# SCH_ZX_WiFi_2023-12-15.net
KiCad netlist of a schematic drawn in EasyEDA
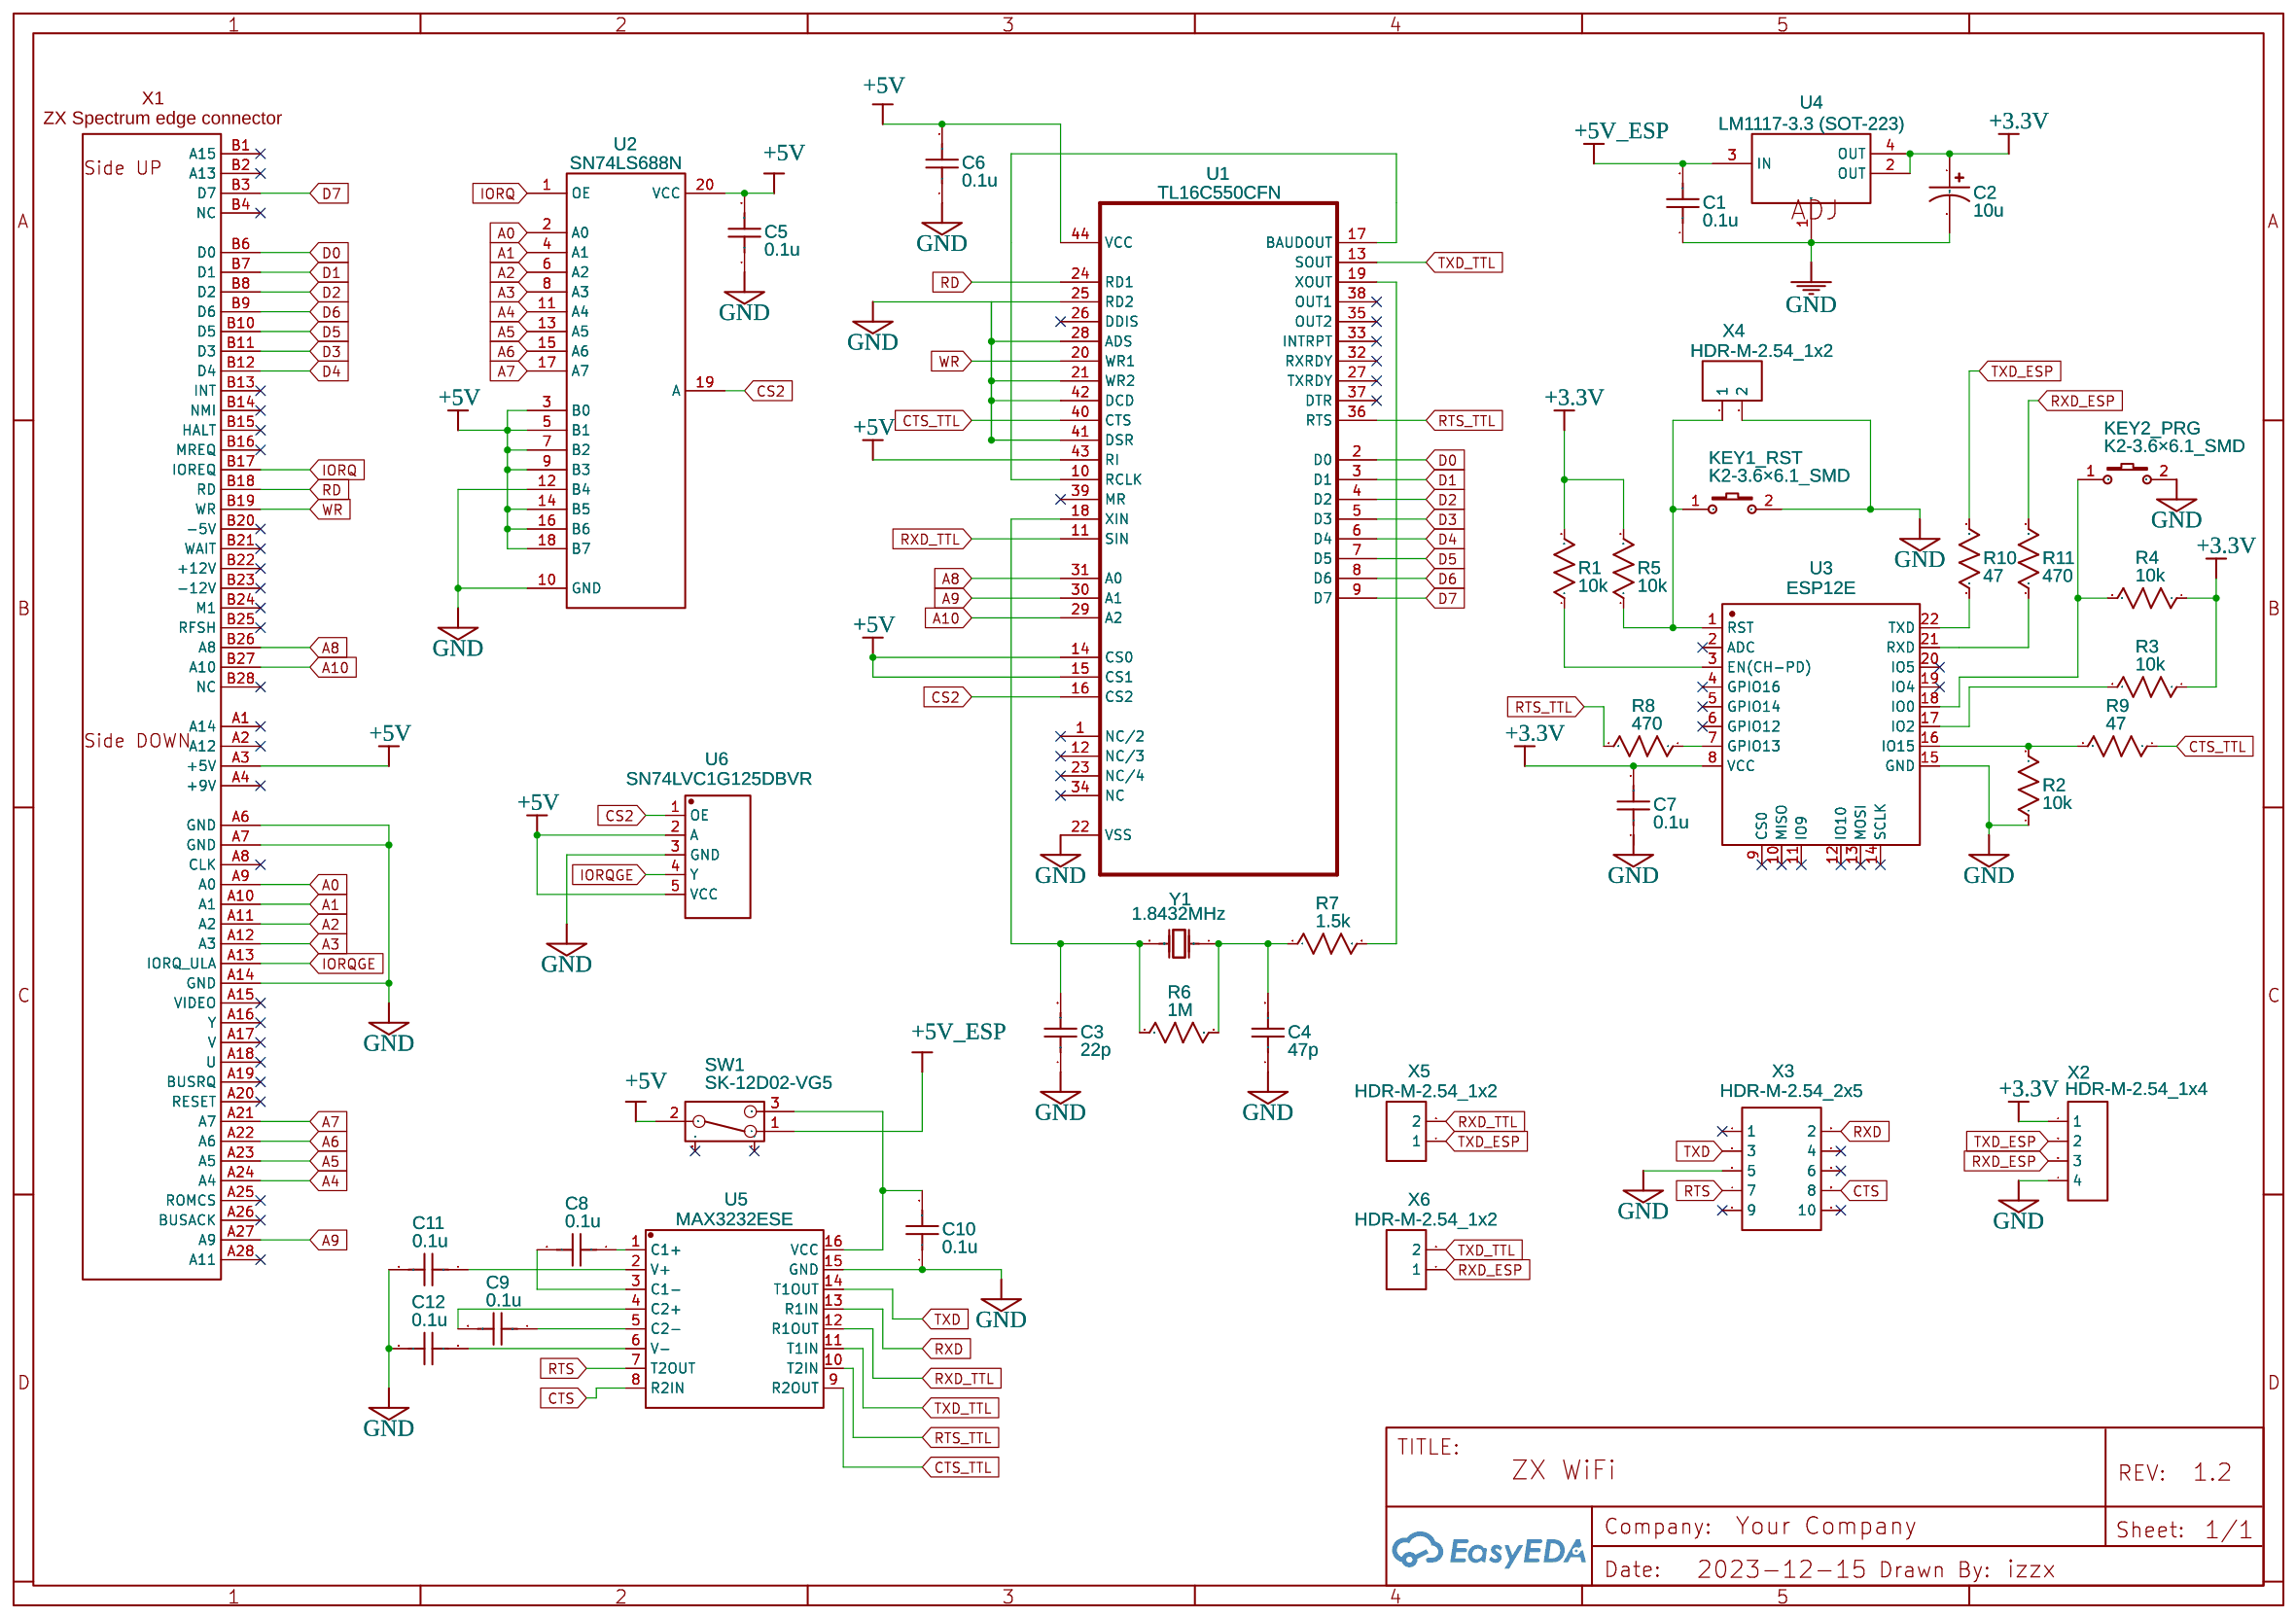
[diagram p0: schematic sheet]

(export (version "E")
  (design (tool "Eeschema 10.0.6"))
  (components
    (comp (ref "C1") (value "0.1u") (libsource (lib "") (part "C_0805_US_1")))
    (comp (ref "C2") (value "10u") (libsource (lib "") (part "C_Tan_SMD_A_US")))
    (comp (ref "C3") (value "22p") (libsource (lib "") (part "C_0805_US_1")))
    (comp (ref "C4") (value "47p") (libsource (lib "") (part "C_0805_US_1")))
    (comp (ref "C5") (value "0.1u") (libsource (lib "") (part "C_0805_US_1")))
    (comp (ref "C6") (value "0.1u") (libsource (lib "") (part "C_0805_US_1")))
    (comp (ref "C7") (value "0.1u") (libsource (lib "") (part "C_0805_US_1")))
    (comp (ref "C8") (value "0.1u") (libsource (lib "") (part "C_0805_US")))
    (comp (ref "C9") (value "0.1u") (libsource (lib "") (part "C_0805_US")))
    (comp (ref "C10") (value "0.1u") (libsource (lib "") (part "C_0805_US_1")))
    (comp (ref "C11") (value "0.1u") (libsource (lib "") (part "C_0805_US")))
    (comp (ref "C12") (value "0.1u") (libsource (lib "") (part "C_0805_US")))
    (comp (ref "KEY1_RST")
      (value "K2-3.6×6.1_SMD")
      (fields (field (name "Manufacturer Part") "K2-1107ST-A4SW-06"))
      (libsource (lib "") (part "K2-3.6×6.1_SMD"))
    )
    (comp (ref "KEY2_PRG")
      (value "K2-3.6×6.1_SMD")
      (fields (field (name "Manufacturer Part") "K2-1107ST-A4SW-06"))
      (libsource (lib "") (part "K2-3.6×6.1_SMD_1"))
    )
    (comp (ref "R1") (value "10k") (libsource (lib "") (part "R_0805_US_1")))
    (comp (ref "R2") (value "10k") (libsource (lib "") (part "R_0805_US_1")))
    (comp (ref "R3") (value "10k") (libsource (lib "") (part "R_0805_US_2")))
    (comp (ref "R4") (value "10k") (libsource (lib "") (part "R_0805_US_2")))
    (comp (ref "R5") (value "10k") (libsource (lib "") (part "R_0805_US_1")))
    (comp (ref "R6") (value "1M") (libsource (lib "") (part "R_0805_US")))
    (comp (ref "R7") (value "1.5k") (libsource (lib "") (part "R_0805_US")))
    (comp (ref "R8") (value "470") (libsource (lib "") (part "R_0805_US_2")))
    (comp (ref "R9") (value "47") (libsource (lib "") (part "R_0805_US_2")))
    (comp (ref "R10") (value "47") (libsource (lib "") (part "R_0805_US_1")))
    (comp (ref "R11") (value "470") (libsource (lib "") (part "R_0805_US_1")))
    (comp (ref "SW1")
      (value "SK-12D02-VG5")
      (fields (field (name "Manufacturer") "Rectangular Connectors - Contacts"))
      (libsource (lib "") (part "SK-12D02-VG5"))
    )
    (comp (ref "U1") (value "TL16C550CFN") (libsource (lib "") (part "TL16C550CFN")))
    (comp (ref "U2") (value "SN74LS688N") (libsource (lib "") (part "SN74LS688N")))
    (comp (ref "U3") (value "ESP12E") (libsource (lib "") (part "ESP12E/F")))
    (comp (ref "U4")
      (value "LM1117-3.3 (SOT-223)")
      (fields (field (name "Manufacturer Part") "LM317G-AA3-R") (field (name "Manufacturer") "UTC"))
      (libsource (lib "") (part "LM317(SOT-223)"))
    )
    (comp (ref "U5")
      (value "MAX3232ESE")
      (fields (field (name "Manufacturer") "UMW(友台半导体)"))
      (libsource (lib "") (part "MAX3232ESE"))
    )
    (comp (ref "U6")
      (value "SN74LVC1G125DBVR")
      (fields (field (name "Manufacturer") "TI(德州仪器)"))
      (libsource (lib "") (part "SN74LVC1G125DBVR"))
    )
    (comp (ref "X1") (value "ZX SPECTRUM CONNECTOR") (libsource (lib "") (part "ZX SPECTRUM CONNECTOR")))
    (comp (ref "X2") (value "HDR-M-2.54_1x4") (libsource (lib "") (part "HDR-M-2.54_1x4")))
    (comp (ref "X3") (value "HDR-M-2.54_2x5") (libsource (lib "") (part "HDR-M-2.54_2x5")))
    (comp (ref "X4") (value "HDR-M-2.54_1x2") (libsource (lib "") (part "HDR-M-2.54_1x2")))
    (comp (ref "X5") (value "HDR-M-2.54_1x2") (libsource (lib "") (part "HDR-M-2.54_1x2_1")))
    (comp (ref "X6") (value "HDR-M-2.54_1x2") (libsource (lib "") (part "HDR-M-2.54_1x2_1")))
    (comp (ref "Y1")
      (value "1.8432MHz")
      (fields (field (name "Manufacturer Part") "X49UD3579MSD2SC") (field (name "Manufacturer") "ValuePro"))
      (libsource (lib "") (part "X49UD3579MSD2SC"))
    )
  )
  (nets
    (net (code "1") (name "+3.3V") (class "Default")
      (node (ref "C2") (pin "1") (pinfunction "1_1") (pintype "unspecified"))
      (node (ref "C7") (pin "2") (pinfunction "2_2") (pintype "unspecified"))
      (node (ref "R1") (pin "2") (pinfunction "2_2") (pintype "unspecified"))
      (node (ref "R3") (pin "1") (pinfunction "1_1") (pintype "unspecified"))
      (node (ref "R4") (pin "1") (pinfunction "1_1") (pintype "unspecified"))
      (node (ref "R5") (pin "2") (pinfunction "2_2") (pintype "unspecified"))
      (node (ref "U3") (pin "8") (pinfunction "VCC_8") (pintype "unspecified"))
      (node (ref "U4") (pin "2") (pinfunction "OUT_2") (pintype "passive"))
      (node (ref "U4") (pin "4") (pinfunction "OUT_4") (pintype "passive"))
      (node (ref "X2") (pin "1") (pinfunction "1_1") (pintype "unspecified"))
    )
    (net (code "2") (name "+5V") (class "Default")
      (node (ref "C5") (pin "2") (pinfunction "2_2") (pintype "unspecified"))
      (node (ref "C6") (pin "2") (pinfunction "2_2") (pintype "unspecified"))
      (node (ref "SW1") (pin "2") (pinfunction "2_2") (pintype "unspecified"))
      (node (ref "U1") (pin "14") (pinfunction "CS0_14") (pintype "input"))
      (node (ref "U1") (pin "15") (pinfunction "CS1_15") (pintype "input"))
      (node (ref "U1") (pin "43") (pinfunction "RI_43") (pintype "input"))
      (node (ref "U1") (pin "44") (pinfunction "VCC_44") (pintype "passive"))
      (node (ref "U2") (pin "14") (pinfunction "B5_14") (pintype "unspecified"))
      (node (ref "U2") (pin "16") (pinfunction "B6_16") (pintype "unspecified"))
      (node (ref "U2") (pin "18") (pinfunction "B7_18") (pintype "unspecified"))
      (node (ref "U2") (pin "20") (pinfunction "VCC_20") (pintype "passive"))
      (node (ref "U2") (pin "3") (pinfunction "B0_3") (pintype "unspecified"))
      (node (ref "U2") (pin "5") (pinfunction "B1_5") (pintype "unspecified"))
      (node (ref "U2") (pin "7") (pinfunction "B2_7") (pintype "unspecified"))
      (node (ref "U2") (pin "9") (pinfunction "B3_9") (pintype "unspecified"))
      (node (ref "U6") (pin "2") (pinfunction "A_2") (pintype "unspecified"))
      (node (ref "U6") (pin "5") (pinfunction "VCC_5") (pintype "unspecified"))
      (node (ref "X1") (pin "A3") (pinfunction "+5V_A3") (pintype "unspecified"))
    )
    (net (code "3") (name "+5V_ESP") (class "Default")
      (node (ref "C1") (pin "2") (pinfunction "2_2") (pintype "unspecified"))
      (node (ref "SW1") (pin "1") (pinfunction "1_1") (pintype "unspecified"))
      (node (ref "U4") (pin "3") (pinfunction "IN_3") (pintype "passive"))
    )
    (net (code "4") (name "A0") (class "Default")
      (node (ref "U2") (pin "2") (pinfunction "A0_2") (pintype "unspecified"))
      (node (ref "X1") (pin "A9") (pinfunction "A0_A9") (pintype "unspecified"))
    )
    (net (code "5") (name "A1") (class "Default")
      (node (ref "U2") (pin "4") (pinfunction "A1_4") (pintype "unspecified"))
      (node (ref "X1") (pin "A10") (pinfunction "A1_A10") (pintype "unspecified"))
    )
    (net (code "6") (name "A2") (class "Default")
      (node (ref "U2") (pin "6") (pinfunction "A2_6") (pintype "unspecified"))
      (node (ref "X1") (pin "A11") (pinfunction "A2_A11") (pintype "unspecified"))
    )
    (net (code "7") (name "A3") (class "Default")
      (node (ref "U2") (pin "8") (pinfunction "A3_8") (pintype "unspecified"))
      (node (ref "X1") (pin "A12") (pinfunction "A3_A12") (pintype "unspecified"))
    )
    (net (code "8") (name "A4") (class "Default")
      (node (ref "U2") (pin "11") (pinfunction "A4_11") (pintype "unspecified"))
      (node (ref "X1") (pin "A24") (pinfunction "A4_A24") (pintype "unspecified"))
    )
    (net (code "9") (name "A5") (class "Default")
      (node (ref "U2") (pin "13") (pinfunction "A5_13") (pintype "unspecified"))
      (node (ref "X1") (pin "A23") (pinfunction "A5_A23") (pintype "unspecified"))
    )
    (net (code "10") (name "A6") (class "Default")
      (node (ref "U2") (pin "15") (pinfunction "A6_15") (pintype "unspecified"))
      (node (ref "X1") (pin "A22") (pinfunction "A6_A22") (pintype "unspecified"))
    )
    (net (code "11") (name "A7") (class "Default")
      (node (ref "U2") (pin "17") (pinfunction "A7_17") (pintype "unspecified"))
      (node (ref "X1") (pin "A21") (pinfunction "A7_A21") (pintype "unspecified"))
    )
    (net (code "12") (name "A8") (class "Default")
      (node (ref "U1") (pin "31") (pinfunction "A0_31") (pintype "input"))
      (node (ref "X1") (pin "B26") (pinfunction "A8_B26") (pintype "unspecified"))
    )
    (net (code "13") (name "A9") (class "Default")
      (node (ref "U1") (pin "30") (pinfunction "A1_30") (pintype "input"))
      (node (ref "X1") (pin "A27") (pinfunction "A9_A27") (pintype "unspecified"))
    )
    (net (code "14") (name "A10") (class "Default")
      (node (ref "U1") (pin "29") (pinfunction "A2_29") (pintype "input"))
      (node (ref "X1") (pin "B27") (pinfunction "A10_B27") (pintype "unspecified"))
    )
    (net (code "15") (name "CS2") (class "Default")
      (node (ref "U1") (pin "16") (pinfunction "CS2_16") (pintype "input"))
      (node (ref "U2") (pin "19") (pinfunction "A_19") (pintype "output"))
      (node (ref "U6") (pin "1") (pinfunction "OE_1") (pintype "unspecified"))
    )
    (net (code "16") (name "CTS") (class "Default")
      (node (ref "U5") (pin "8") (pinfunction "R2IN_8") (pintype "unspecified"))
      (node (ref "X3") (pin "8") (pinfunction "8_8") (pintype "unspecified"))
    )
    (net (code "17") (name "CTS_TTL") (class "Default")
      (node (ref "R9") (pin "1") (pinfunction "1_1") (pintype "unspecified"))
      (node (ref "U1") (pin "40") (pinfunction "CTS_40") (pintype "input"))
      (node (ref "U5") (pin "9") (pinfunction "R2OUT_9") (pintype "unspecified"))
    )
    (net (code "18") (name "D0") (class "Default")
      (node (ref "U1") (pin "2") (pinfunction "D0_2") (pintype "unspecified"))
      (node (ref "X1") (pin "B6") (pinfunction "D0_B6") (pintype "bidirectional"))
    )
    (net (code "19") (name "D1") (class "Default")
      (node (ref "U1") (pin "3") (pinfunction "D1_3") (pintype "unspecified"))
      (node (ref "X1") (pin "B7") (pinfunction "D1_B7") (pintype "bidirectional"))
    )
    (net (code "20") (name "D2") (class "Default")
      (node (ref "U1") (pin "4") (pinfunction "D2_4") (pintype "unspecified"))
      (node (ref "X1") (pin "B8") (pinfunction "D2_B8") (pintype "bidirectional"))
    )
    (net (code "21") (name "D3") (class "Default")
      (node (ref "U1") (pin "5") (pinfunction "D3_5") (pintype "unspecified"))
      (node (ref "X1") (pin "B11") (pinfunction "D3_B11") (pintype "unspecified"))
    )
    (net (code "22") (name "D4") (class "Default")
      (node (ref "U1") (pin "6") (pinfunction "D4_6") (pintype "unspecified"))
      (node (ref "X1") (pin "B12") (pinfunction "D4_B12") (pintype "unspecified"))
    )
    (net (code "23") (name "D5") (class "Default")
      (node (ref "U1") (pin "7") (pinfunction "D5_7") (pintype "unspecified"))
      (node (ref "X1") (pin "B10") (pinfunction "D5_B10") (pintype "bidirectional"))
    )
    (net (code "24") (name "D6") (class "Default")
      (node (ref "U1") (pin "8") (pinfunction "D6_8") (pintype "unspecified"))
      (node (ref "X1") (pin "B9") (pinfunction "D6_B9") (pintype "unspecified"))
    )
    (net (code "25") (name "D7") (class "Default")
      (node (ref "U1") (pin "9") (pinfunction "D7_9") (pintype "unspecified"))
      (node (ref "X1") (pin "B3") (pinfunction "D7_B3") (pintype "bidirectional"))
    )
    (net (code "26") (name "GND") (class "Default")
      (node (ref "C1") (pin "1") (pinfunction "1_1") (pintype "unspecified"))
      (node (ref "C10") (pin "1") (pinfunction "1_1") (pintype "unspecified"))
      (node (ref "C11") (pin "2") (pinfunction "2_2") (pintype "unspecified"))
      (node (ref "C12") (pin "2") (pinfunction "2_2") (pintype "unspecified"))
      (node (ref "C2") (pin "2") (pinfunction "2_2") (pintype "unspecified"))
      (node (ref "C3") (pin "1") (pinfunction "1_1") (pintype "unspecified"))
      (node (ref "C4") (pin "1") (pinfunction "1_1") (pintype "unspecified"))
      (node (ref "C5") (pin "1") (pinfunction "1_1") (pintype "unspecified"))
      (node (ref "C6") (pin "1") (pinfunction "1_1") (pintype "unspecified"))
      (node (ref "C7") (pin "1") (pinfunction "1_1") (pintype "unspecified"))
      (node (ref "KEY1_RST") (pin "2") (pinfunction "2_2") (pintype "unspecified"))
      (node (ref "KEY2_PRG") (pin "2") (pinfunction "2_2") (pintype "unspecified"))
      (node (ref "R2") (pin "1") (pinfunction "1_1") (pintype "unspecified"))
      (node (ref "U1") (pin "21") (pinfunction "WR2_21") (pintype "input"))
      (node (ref "U1") (pin "22") (pinfunction "VSS_22") (pintype "passive"))
      (node (ref "U1") (pin "25") (pinfunction "RD2_25") (pintype "input"))
      (node (ref "U1") (pin "28") (pinfunction "ADS_28") (pintype "input"))
      (node (ref "U1") (pin "41") (pinfunction "DSR_41") (pintype "input"))
      (node (ref "U1") (pin "42") (pinfunction "DCD_42") (pintype "input"))
      (node (ref "U2") (pin "10") (pinfunction "GND_10") (pintype "passive"))
      (node (ref "U2") (pin "12") (pinfunction "B4_12") (pintype "unspecified"))
      (node (ref "U3") (pin "15") (pinfunction "GND_15") (pintype "unspecified"))
      (node (ref "U4") (pin "1") (pinfunction "ADJ_1") (pintype "passive"))
      (node (ref "U5") (pin "15") (pinfunction "GND_15") (pintype "unspecified"))
      (node (ref "U6") (pin "3") (pinfunction "GND_3") (pintype "unspecified"))
      (node (ref "X1") (pin "A14") (pinfunction "GND_A14") (pintype "unspecified"))
      (node (ref "X1") (pin "A6") (pinfunction "GND_A6") (pintype "unspecified"))
      (node (ref "X1") (pin "A7") (pinfunction "GND_A7") (pintype "unspecified"))
      (node (ref "X2") (pin "4") (pinfunction "4_4") (pintype "unspecified"))
      (node (ref "X3") (pin "5") (pinfunction "5_5") (pintype "unspecified"))
      (node (ref "X4") (pin "2") (pinfunction "2_2") (pintype "unspecified"))
    )
    (net (code "27") (name "IORQ") (class "Default")
      (node (ref "U2") (pin "1") (pinfunction "OE_1") (pintype "unspecified"))
      (node (ref "X1") (pin "B17") (pinfunction "IOREQ_B17") (pintype "unspecified"))
    )
    (net (code "28") (name "IORQGE") (class "Default")
      (node (ref "U6") (pin "4") (pinfunction "Y_4") (pintype "unspecified"))
      (node (ref "X1") (pin "A13") (pinfunction "IORQ_ULA_A13") (pintype "unspecified"))
    )
    (net (code "29") (name "Net-(U1-BAUDOUT)") (class "Default")
      (node (ref "U1") (pin "10") (pinfunction "RCLK_10") (pintype "input"))
      (node (ref "U1") (pin "17") (pinfunction "BAUDOUT_17") (pintype "output"))
    )
    (net (code "30") (name "Net-(U1-XIN)") (class "Default")
      (node (ref "C3") (pin "2") (pinfunction "2_2") (pintype "unspecified"))
      (node (ref "R6") (pin "1") (pinfunction "1_1") (pintype "unspecified"))
      (node (ref "U1") (pin "18") (pinfunction "XIN_18") (pintype "input"))
      (node (ref "Y1") (pin "2") (pinfunction "OSC2_2") (pintype "input"))
    )
    (net (code "31") (name "Net-(U1-XOUT)") (class "Default")
      (node (ref "R7") (pin "2") (pinfunction "2_2") (pintype "unspecified"))
      (node (ref "U1") (pin "19") (pinfunction "XOUT_19") (pintype "output"))
    )
    (net (code "32") (name "Net-(U3-EN(CH-PD))") (class "Default")
      (node (ref "R1") (pin "1") (pinfunction "1_1") (pintype "unspecified"))
      (node (ref "U3") (pin "3") (pinfunction "EN(CH-PD)_3") (pintype "unspecified"))
    )
    (net (code "33") (name "Net-(U3-GPIO13)") (class "Default")
      (node (ref "R8") (pin "1") (pinfunction "1_1") (pintype "unspecified"))
      (node (ref "U3") (pin "7") (pinfunction "GPIO13_7") (pintype "unspecified"))
    )
    (net (code "34") (name "Net-(U3-IO0)") (class "Default")
      (node (ref "KEY2_PRG") (pin "1") (pinfunction "1_1") (pintype "unspecified"))
      (node (ref "R4") (pin "2") (pinfunction "2_2") (pintype "unspecified"))
      (node (ref "U3") (pin "18") (pinfunction "IO0_18") (pintype "unspecified"))
    )
    (net (code "35") (name "Net-(U3-IO2)") (class "Default")
      (node (ref "R3") (pin "2") (pinfunction "2_2") (pintype "unspecified"))
      (node (ref "U3") (pin "17") (pinfunction "IO2_17") (pintype "unspecified"))
    )
    (net (code "36") (name "Net-(U3-IO15)") (class "Default")
      (node (ref "R2") (pin "2") (pinfunction "2_2") (pintype "unspecified"))
      (node (ref "R9") (pin "2") (pinfunction "2_2") (pintype "unspecified"))
      (node (ref "U3") (pin "16") (pinfunction "IO15_16") (pintype "unspecified"))
    )
    (net (code "37") (name "Net-(U3-RST)") (class "Default")
      (node (ref "KEY1_RST") (pin "1") (pinfunction "1_1") (pintype "unspecified"))
      (node (ref "R5") (pin "1") (pinfunction "1_1") (pintype "unspecified"))
      (node (ref "U3") (pin "1") (pinfunction "RST_1") (pintype "unspecified"))
      (node (ref "X4") (pin "1") (pinfunction "1_1") (pintype "unspecified"))
    )
    (net (code "38") (name "Net-(U3-RXD)") (class "Default")
      (node (ref "R11") (pin "1") (pinfunction "1_1") (pintype "unspecified"))
      (node (ref "U3") (pin "21") (pinfunction "RXD_21") (pintype "unspecified"))
    )
    (net (code "39") (name "Net-(U3-TXD)") (class "Default")
      (node (ref "R10") (pin "1") (pinfunction "1_1") (pintype "unspecified"))
      (node (ref "U3") (pin "22") (pinfunction "TXD_22") (pintype "unspecified"))
    )
    (net (code "40") (name "Net-(U5-C1+)") (class "Default")
      (node (ref "C8") (pin "1") (pinfunction "1_1") (pintype "unspecified"))
      (node (ref "U5") (pin "1") (pinfunction "C1+_1") (pintype "unspecified"))
    )
    (net (code "41") (name "Net-(U5-C1-)") (class "Default")
      (node (ref "C8") (pin "2") (pinfunction "2_2") (pintype "unspecified"))
      (node (ref "U5") (pin "3") (pinfunction "C1-_3") (pintype "unspecified"))
    )
    (net (code "42") (name "Net-(U5-C2+)") (class "Default")
      (node (ref "C9") (pin "2") (pinfunction "2_2") (pintype "unspecified"))
      (node (ref "U5") (pin "4") (pinfunction "C2+_4") (pintype "unspecified"))
    )
    (net (code "43") (name "Net-(U5-C2-)") (class "Default")
      (node (ref "C9") (pin "1") (pinfunction "1_1") (pintype "unspecified"))
      (node (ref "U5") (pin "5") (pinfunction "C2-_5") (pintype "unspecified"))
    )
    (net (code "44") (name "Net-(U5-V+)") (class "Default")
      (node (ref "C11") (pin "1") (pinfunction "1_1") (pintype "unspecified"))
      (node (ref "U5") (pin "2") (pinfunction "V+_2") (pintype "unspecified"))
    )
    (net (code "45") (name "Net-(U5-V-)") (class "Default")
      (node (ref "C12") (pin "1") (pinfunction "1_1") (pintype "unspecified"))
      (node (ref "U5") (pin "6") (pinfunction "V-_6") (pintype "unspecified"))
    )
    (net (code "46") (name "Net-(U5-VCC)") (class "Default")
      (node (ref "C10") (pin "2") (pinfunction "2_2") (pintype "unspecified"))
      (node (ref "SW1") (pin "3") (pinfunction "3_3") (pintype "unspecified"))
      (node (ref "U5") (pin "16") (pinfunction "VCC_16") (pintype "unspecified"))
    )
    (net (code "47") (name "Net-(Y1-OSC1)") (class "Default")
      (node (ref "C4") (pin "2") (pinfunction "2_2") (pintype "unspecified"))
      (node (ref "R6") (pin "2") (pinfunction "2_2") (pintype "unspecified"))
      (node (ref "R7") (pin "1") (pinfunction "1_1") (pintype "unspecified"))
      (node (ref "Y1") (pin "1") (pinfunction "OSC1_1") (pintype "input"))
    )
    (net (code "48") (name "RD") (class "Default")
      (node (ref "U1") (pin "24") (pinfunction "RD1_24") (pintype "input"))
      (node (ref "X1") (pin "B18") (pinfunction "RD_B18") (pintype "unspecified"))
    )
    (net (code "49") (name "RTS") (class "Default")
      (node (ref "U5") (pin "7") (pinfunction "T2OUT_7") (pintype "unspecified"))
      (node (ref "X3") (pin "7") (pinfunction "7_7") (pintype "unspecified"))
    )
    (net (code "50") (name "RTS_TTL") (class "Default")
      (node (ref "R8") (pin "2") (pinfunction "2_2") (pintype "unspecified"))
      (node (ref "U1") (pin "36") (pinfunction "RTS_36") (pintype "output"))
      (node (ref "U5") (pin "10") (pinfunction "T2IN_10") (pintype "unspecified"))
    )
    (net (code "51") (name "RXD") (class "Default")
      (node (ref "U5") (pin "13") (pinfunction "R1IN_13") (pintype "unspecified"))
      (node (ref "X3") (pin "2") (pinfunction "2_2") (pintype "unspecified"))
    )
    (net (code "52") (name "RXD_ESP") (class "Default")
      (node (ref "R11") (pin "2") (pinfunction "2_2") (pintype "unspecified"))
      (node (ref "X2") (pin "3") (pinfunction "3_3") (pintype "unspecified"))
      (node (ref "X6") (pin "1") (pinfunction "1_1") (pintype "unspecified"))
    )
    (net (code "53") (name "RXD_TTL") (class "Default")
      (node (ref "U1") (pin "11") (pinfunction "SIN_11") (pintype "input"))
      (node (ref "U5") (pin "12") (pinfunction "R1OUT_12") (pintype "unspecified"))
      (node (ref "X5") (pin "2") (pinfunction "2_2") (pintype "unspecified"))
    )
    (net (code "54") (name "TXD") (class "Default")
      (node (ref "U5") (pin "14") (pinfunction "T1OUT_14") (pintype "unspecified"))
      (node (ref "X3") (pin "3") (pinfunction "3_3") (pintype "unspecified"))
    )
    (net (code "55") (name "TXD_ESP") (class "Default")
      (node (ref "R10") (pin "2") (pinfunction "2_2") (pintype "unspecified"))
      (node (ref "X2") (pin "2") (pinfunction "2_2") (pintype "unspecified"))
      (node (ref "X5") (pin "1") (pinfunction "1_1") (pintype "unspecified"))
    )
    (net (code "56") (name "TXD_TTL") (class "Default")
      (node (ref "U1") (pin "13") (pinfunction "SOUT_13") (pintype "output"))
      (node (ref "U5") (pin "11") (pinfunction "T1IN_11") (pintype "unspecified"))
      (node (ref "X6") (pin "2") (pinfunction "2_2") (pintype "unspecified"))
    )
    (net (code "57") (name "WR") (class "Default")
      (node (ref "U1") (pin "20") (pinfunction "WR1_20") (pintype "input"))
      (node (ref "X1") (pin "B19") (pinfunction "WR_B19") (pintype "unspecified"))
    )
    (net (code "58") (name "unconnected-(SW1-Pad4)") (class "Default")
      (node (ref "SW1") (pin "4") (pinfunction "4_4") (pintype "unspecified+no_connect"))
    )
    (net (code "59") (name "unconnected-(SW1-Pad5)") (class "Default")
      (node (ref "SW1") (pin "5") (pinfunction "5_5") (pintype "unspecified+no_connect"))
    )
    (net (code "60") (name "unconnected-(U1-DDIS-Pad26)") (class "Default")
      (node (ref "U1") (pin "26") (pinfunction "DDIS_26") (pintype "input+no_connect"))
    )
    (net (code "61") (name "unconnected-(U1-DTR-Pad37)") (class "Default")
      (node (ref "U1") (pin "37") (pinfunction "DTR_37") (pintype "output+no_connect"))
    )
    (net (code "62") (name "unconnected-(U1-INTRPT-Pad33)") (class "Default")
      (node (ref "U1") (pin "33") (pinfunction "INTRPT_33") (pintype "output+no_connect"))
    )
    (net (code "63") (name "unconnected-(U1-MR-Pad39)") (class "Default")
      (node (ref "U1") (pin "39") (pinfunction "MR_39") (pintype "input+no_connect"))
    )
    (net (code "64") (name "unconnected-(U1-NC-Pad34)") (class "Default")
      (node (ref "U1") (pin "34") (pinfunction "NC_34") (pintype "unspecified+no_connect"))
    )
    (net (code "65") (name "unconnected-(U1-NC{slash}2-Pad1)") (class "Default")
      (node (ref "U1") (pin "1") (pinfunction "NC/2_1") (pintype "unspecified+no_connect"))
    )
    (net (code "66") (name "unconnected-(U1-NC{slash}3-Pad12)") (class "Default")
      (node (ref "U1") (pin "12") (pinfunction "NC/3_12") (pintype "unspecified+no_connect"))
    )
    (net (code "67") (name "unconnected-(U1-NC{slash}4-Pad23)") (class "Default")
      (node (ref "U1") (pin "23") (pinfunction "NC/4_23") (pintype "unspecified+no_connect"))
    )
    (net (code "68") (name "unconnected-(U1-OUT1-Pad38)") (class "Default")
      (node (ref "U1") (pin "38") (pinfunction "OUT1_38") (pintype "output+no_connect"))
    )
    (net (code "69") (name "unconnected-(U1-OUT2-Pad35)") (class "Default")
      (node (ref "U1") (pin "35") (pinfunction "OUT2_35") (pintype "output+no_connect"))
    )
    (net (code "70") (name "unconnected-(U1-RXRDY-Pad32)") (class "Default")
      (node (ref "U1") (pin "32") (pinfunction "RXRDY_32") (pintype "output+no_connect"))
    )
    (net (code "71") (name "unconnected-(U1-TXRDY-Pad27)") (class "Default")
      (node (ref "U1") (pin "27") (pinfunction "TXRDY_27") (pintype "output+no_connect"))
    )
    (net (code "72") (name "unconnected-(U3-ADC-Pad2)") (class "Default")
      (node (ref "U3") (pin "2") (pinfunction "ADC_2") (pintype "unspecified+no_connect"))
    )
    (net (code "73") (name "unconnected-(U3-CS0-Pad9)") (class "Default")
      (node (ref "U3") (pin "9") (pinfunction "CS0_9") (pintype "unspecified+no_connect"))
    )
    (net (code "74") (name "unconnected-(U3-GPIO12-Pad6)") (class "Default")
      (node (ref "U3") (pin "6") (pinfunction "GPIO12_6") (pintype "unspecified+no_connect"))
    )
    (net (code "75") (name "unconnected-(U3-GPIO14-Pad5)") (class "Default")
      (node (ref "U3") (pin "5") (pinfunction "GPIO14_5") (pintype "unspecified+no_connect"))
    )
    (net (code "76") (name "unconnected-(U3-GPIO16-Pad4)") (class "Default")
      (node (ref "U3") (pin "4") (pinfunction "GPIO16_4") (pintype "unspecified+no_connect"))
    )
    (net (code "77") (name "unconnected-(U3-IO4-Pad19)") (class "Default")
      (node (ref "U3") (pin "19") (pinfunction "IO4_19") (pintype "unspecified+no_connect"))
    )
    (net (code "78") (name "unconnected-(U3-IO5-Pad20)") (class "Default")
      (node (ref "U3") (pin "20") (pinfunction "IO5_20") (pintype "unspecified+no_connect"))
    )
    (net (code "79") (name "unconnected-(U3-IO9-Pad11)") (class "Default")
      (node (ref "U3") (pin "11") (pinfunction "IO9_11") (pintype "unspecified+no_connect"))
    )
    (net (code "80") (name "unconnected-(U3-IO10-Pad12)") (class "Default")
      (node (ref "U3") (pin "12") (pinfunction "IO10_12") (pintype "unspecified+no_connect"))
    )
    (net (code "81") (name "unconnected-(U3-MISO-Pad10)") (class "Default")
      (node (ref "U3") (pin "10") (pinfunction "MISO_10") (pintype "unspecified+no_connect"))
    )
    (net (code "82") (name "unconnected-(U3-MOSI-Pad13)") (class "Default")
      (node (ref "U3") (pin "13") (pinfunction "MOSI_13") (pintype "unspecified+no_connect"))
    )
    (net (code "83") (name "unconnected-(U3-SCLK-Pad14)") (class "Default")
      (node (ref "U3") (pin "14") (pinfunction "SCLK_14") (pintype "unspecified+no_connect"))
    )
    (net (code "84") (name "unconnected-(X1-+9V-PadA4)") (class "Default")
      (node (ref "X1") (pin "A4") (pinfunction "+9V_A4") (pintype "unspecified+no_connect"))
    )
    (net (code "85") (name "unconnected-(X1-+12V-PadB22)") (class "Default")
      (node (ref "X1") (pin "B22") (pinfunction "+12V_B22") (pintype "unspecified+no_connect"))
    )
    (net (code "86") (name "unconnected-(X1--5V-PadB20)") (class "Default")
      (node (ref "X1") (pin "B20") (pinfunction "-5V_B20") (pintype "unspecified+no_connect"))
    )
    (net (code "87") (name "unconnected-(X1--12V-PadB23)") (class "Default")
      (node (ref "X1") (pin "B23") (pinfunction "-12V_B23") (pintype "unspecified+no_connect"))
    )
    (net (code "88") (name "unconnected-(X1-A11-PadA28)") (class "Default")
      (node (ref "X1") (pin "A28") (pinfunction "A11_A28") (pintype "unspecified+no_connect"))
    )
    (net (code "89") (name "unconnected-(X1-A12-PadA2)") (class "Default")
      (node (ref "X1") (pin "A2") (pinfunction "A12_A2") (pintype "unspecified+no_connect"))
    )
    (net (code "90") (name "unconnected-(X1-A13-PadB2)") (class "Default")
      (node (ref "X1") (pin "B2") (pinfunction "A13_B2") (pintype "output+no_connect"))
    )
    (net (code "91") (name "unconnected-(X1-A14-PadA1)") (class "Default")
      (node (ref "X1") (pin "A1") (pinfunction "A14_A1") (pintype "unspecified+no_connect"))
    )
    (net (code "92") (name "unconnected-(X1-A15-PadB1)") (class "Default")
      (node (ref "X1") (pin "B1") (pinfunction "A15_B1") (pintype "output+no_connect"))
    )
    (net (code "93") (name "unconnected-(X1-BUSACK-PadA26)") (class "Default")
      (node (ref "X1") (pin "A26") (pinfunction "BUSACK_A26") (pintype "unspecified+no_connect"))
    )
    (net (code "94") (name "unconnected-(X1-BUSRQ-PadA19)") (class "Default")
      (node (ref "X1") (pin "A19") (pinfunction "BUSRQ_A19") (pintype "unspecified+no_connect"))
    )
    (net (code "95") (name "unconnected-(X1-CLK-PadA8)") (class "Default")
      (node (ref "X1") (pin "A8") (pinfunction "CLK_A8") (pintype "unspecified+no_connect"))
    )
    (net (code "96") (name "unconnected-(X1-HALT-PadB15)") (class "Default")
      (node (ref "X1") (pin "B15") (pinfunction "HALT_B15") (pintype "unspecified+no_connect"))
    )
    (net (code "97") (name "unconnected-(X1-INT-PadB13)") (class "Default")
      (node (ref "X1") (pin "B13") (pinfunction "INT_B13") (pintype "unspecified+no_connect"))
    )
    (net (code "98") (name "unconnected-(X1-M1-PadB24)") (class "Default")
      (node (ref "X1") (pin "B24") (pinfunction "M1_B24") (pintype "unspecified+no_connect"))
    )
    (net (code "99") (name "unconnected-(X1-MREQ-PadB16)") (class "Default")
      (node (ref "X1") (pin "B16") (pinfunction "MREQ_B16") (pintype "unspecified+no_connect"))
    )
    (net (code "100") (name "unconnected-(X1-NC-PadB4)") (class "Default")
      (node (ref "X1") (pin "B4") (pinfunction "NC_B4") (pintype "unspecified+no_connect"))
    )
    (net (code "101") (name "unconnected-(X1-NC-PadB28)") (class "Default")
      (node (ref "X1") (pin "B28") (pinfunction "NC_B28") (pintype "unspecified+no_connect"))
    )
    (net (code "102") (name "unconnected-(X1-NMI-PadB14)") (class "Default")
      (node (ref "X1") (pin "B14") (pinfunction "NMI_B14") (pintype "unspecified+no_connect"))
    )
    (net (code "103") (name "unconnected-(X1-RESET-PadA20)") (class "Default")
      (node (ref "X1") (pin "A20") (pinfunction "RESET_A20") (pintype "unspecified+no_connect"))
    )
    (net (code "104") (name "unconnected-(X1-RFSH-PadB25)") (class "Default")
      (node (ref "X1") (pin "B25") (pinfunction "RFSH_B25") (pintype "unspecified+no_connect"))
    )
    (net (code "105") (name "unconnected-(X1-ROMCS-PadA25)") (class "Default")
      (node (ref "X1") (pin "A25") (pinfunction "ROMCS_A25") (pintype "unspecified+no_connect"))
    )
    (net (code "106") (name "unconnected-(X1-U-PadA18)") (class "Default")
      (node (ref "X1") (pin "A18") (pinfunction "U_A18") (pintype "unspecified+no_connect"))
    )
    (net (code "107") (name "unconnected-(X1-V-PadA17)") (class "Default")
      (node (ref "X1") (pin "A17") (pinfunction "V_A17") (pintype "unspecified+no_connect"))
    )
    (net (code "108") (name "unconnected-(X1-VIDEO-PadA15)") (class "Default")
      (node (ref "X1") (pin "A15") (pinfunction "VIDEO_A15") (pintype "unspecified+no_connect"))
    )
    (net (code "109") (name "unconnected-(X1-WAIT-PadB21)") (class "Default")
      (node (ref "X1") (pin "B21") (pinfunction "WAIT_B21") (pintype "unspecified+no_connect"))
    )
    (net (code "110") (name "unconnected-(X1-Y-PadA16)") (class "Default")
      (node (ref "X1") (pin "A16") (pinfunction "Y_A16") (pintype "unspecified+no_connect"))
    )
    (net (code "111") (name "unconnected-(X3-Pad1)") (class "Default")
      (node (ref "X3") (pin "1") (pinfunction "1_1") (pintype "unspecified+no_connect"))
    )
    (net (code "112") (name "unconnected-(X3-Pad4)") (class "Default")
      (node (ref "X3") (pin "4") (pinfunction "4_4") (pintype "unspecified+no_connect"))
    )
    (net (code "113") (name "unconnected-(X3-Pad6)") (class "Default")
      (node (ref "X3") (pin "6") (pinfunction "6_6") (pintype "unspecified+no_connect"))
    )
    (net (code "114") (name "unconnected-(X3-Pad9)") (class "Default")
      (node (ref "X3") (pin "9") (pinfunction "9_9") (pintype "unspecified+no_connect"))
    )
    (net (code "115") (name "unconnected-(X3-Pad10)") (class "Default")
      (node (ref "X3") (pin "10") (pinfunction "10_10") (pintype "unspecified+no_connect"))
    )
  )
)
